# Sensors.net
KiCad netlist of a schematic drawn in Altium Designer
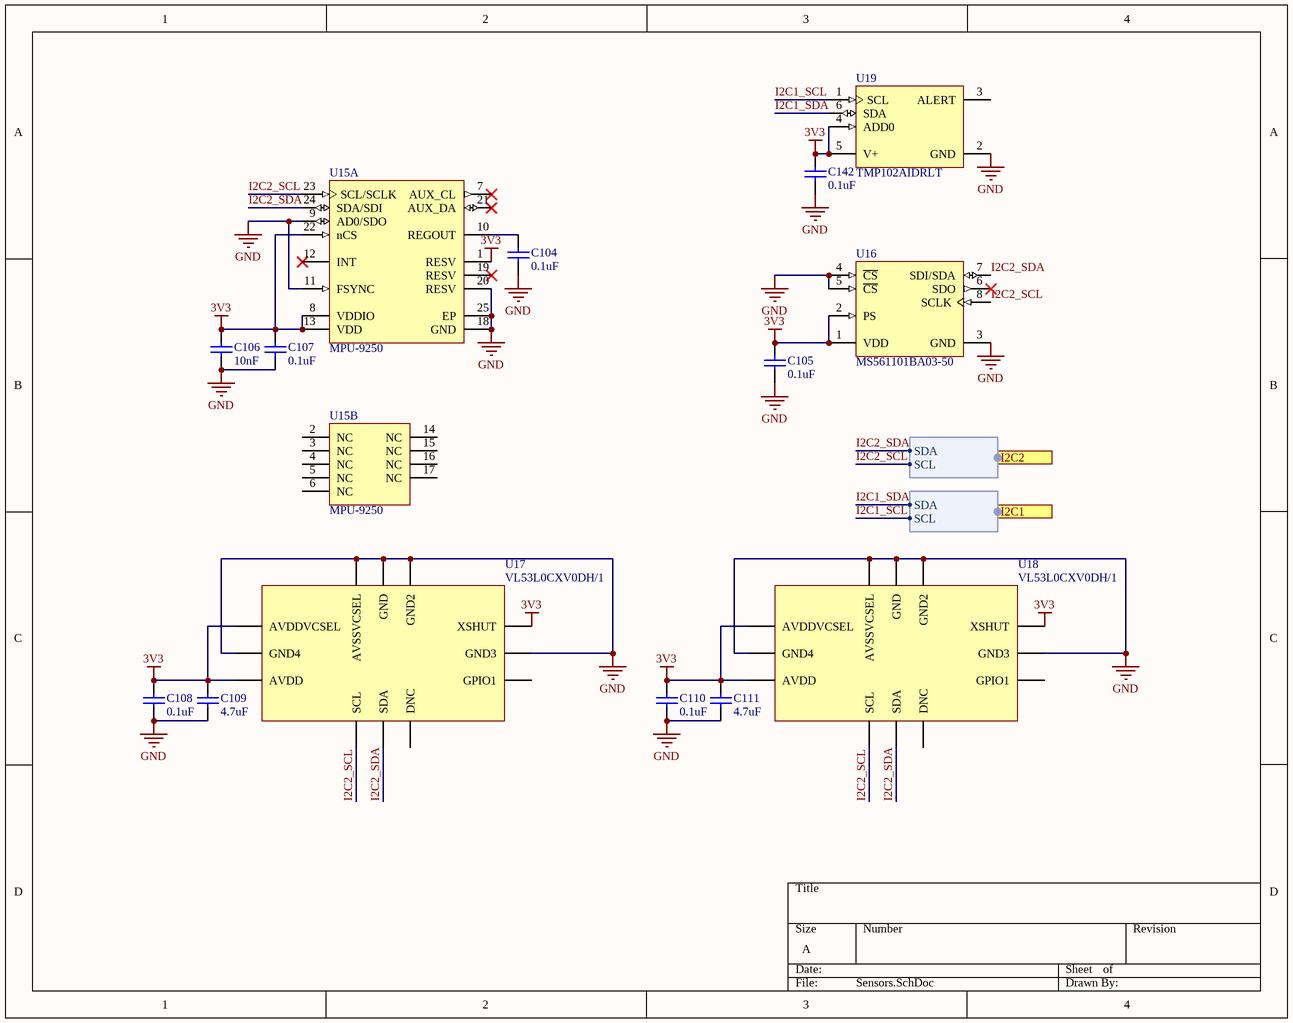
[diagram p0: Sensors.SchDoc]

(export (version "E")
  (design (tool "Eeschema 10.0.6"))
  (components
    (comp (ref "C104")
      (value "0.1uF")
      (footprint "C0402[1005X55]")
      (description "0.1uF 6.3V 10% 0402 (1005 Metric)")
      (fields (field (name "PARTNUMBER") "GRM155R70J104KA01D") (field (name "MANUFACTURER") "Murata"))
      (libsource (lib "Capacitors") (part "CAP_0.1uF_6.3V_0402_10%"))
    )
    (comp (ref "C105")
      (value "0.1uF")
      (footprint "C0402[1005X55]")
      (description "0.1uF 6.3V 10% 0402 (1005 Metric)")
      (fields (field (name "PARTNUMBER") "GRM155R70J104KA01D") (field (name "MANUFACTURER") "Murata"))
      (libsource (lib "Capacitors") (part "CAP_0.1uF_6.3V_0402_10%"))
    )
    (comp (ref "C106")
      (value "10nF")
      (footprint "C0402[1005X55]")
      (description "10nF 50V 10% 0402 (1005 Metric)")
      (fields (field (name "PARTNUMBER") "GCM155R71H103KA55D") (field (name "MANUFACTURER") "Murata"))
      (libsource (lib "Capacitors") (part "CAP_10nF_50V_0402_10%"))
    )
    (comp (ref "C107")
      (value "0.1uF")
      (footprint "C0402[1005X55]")
      (description "0.1uF 6.3V 10% 0402 (1005 Metric)")
      (fields (field (name "PARTNUMBER") "GRM155R70J104KA01D") (field (name "MANUFACTURER") "Murata"))
      (libsource (lib "Capacitors") (part "CAP_0.1uF_6.3V_0402_10%"))
    )
    (comp (ref "C108")
      (value "0.1uF")
      (footprint "C0402[1005X55]")
      (description "0.1uF 6.3V 10% 0402 (1005 Metric)")
      (fields (field (name "PARTNUMBER") "GRM155R70J104KA01D") (field (name "MANUFACTURER") "Murata"))
      (libsource (lib "Capacitors") (part "CAP_0.1uF_6.3V_0402_10%"))
    )
    (comp (ref "C109")
      (value "4.7uF")
      (footprint "C0402[1005X55]")
      (description "4.7uF 6.3V 20% 0402 (1005 Metric)")
      (fields (field (name "PARTNUMBER") "GRM155R60J475ME47D") (field (name "MANUFACTURER") "Murata"))
      (libsource (lib "Capacitors") (part "CAP_4.7uF_6.3V_0402_20%"))
    )
    (comp (ref "C110")
      (value "0.1uF")
      (footprint "C0402[1005X55]")
      (description "0.1uF 6.3V 10% 0402 (1005 Metric)")
      (fields (field (name "PARTNUMBER") "GRM155R70J104KA01D") (field (name "MANUFACTURER") "Murata"))
      (libsource (lib "Capacitors") (part "CAP_0.1uF_6.3V_0402_10%"))
    )
    (comp (ref "C111")
      (value "4.7uF")
      (footprint "C0402[1005X55]")
      (description "4.7uF 6.3V 20% 0402 (1005 Metric)")
      (fields (field (name "PARTNUMBER") "GRM155R60J475ME47D") (field (name "MANUFACTURER") "Murata"))
      (libsource (lib "Capacitors") (part "CAP_4.7uF_6.3V_0402_20%"))
    )
    (comp (ref "C142")
      (value "0.1uF")
      (footprint "C0402[1005X55]")
      (description "0.1uF 6.3V 10% 0402 (1005 Metric)")
      (fields (field (name "PARTNUMBER") "GRM155R70J104KA01D") (field (name "MANUFACTURER") "Murata"))
      (libsource (lib "Capacitors") (part "CAP_0.1uF_6.3V_0402_10%"))
    )
    (comp (ref "U15")
      (value "MPU-9250")
      (footprint "QFN-24 (0.4MM)")
      (fields (field (name "MANUFACTURER") "Invensense"))
      (libsource (lib "ICs") (part "MPU-9250"))
    )
    (comp (ref "U16")
      (value "MS561101BA03-50")
      (footprint "MSI-MS561101BA03-50-8_V")
      (fields (field (name "MANUFACTURER") "Measurement Specialties"))
      (libsource (lib "Altium Content Vault") (part "MSI-MS561101BA03-50-8"))
    )
    (comp (ref "U17")
      (value "VL53L0CXV0DH/1")
      (footprint "LGA-12")
      (description "Optical Sensor Modules Time-of-Flight (ToF) ranging sensor")
      (fields (field (name "MANUFACTURER") "STMicroelectronics"))
      (libsource (lib "ICs") (part "VL53L0CXV0DH/1"))
    )
    (comp (ref "U18")
      (value "VL53L0CXV0DH/1")
      (footprint "LGA-12")
      (description "Optical Sensor Modules Time-of-Flight (ToF) ranging sensor")
      (fields (field (name "MANUFACTURER") "STMicroelectronics"))
      (libsource (lib "ICs") (part "VL53L0CXV0DH/1"))
    )
    (comp (ref "U19")
      (value "TMP102AIDRLT")
      (footprint "DRL0006A_L")
      (libsource (lib "Altium Content Vault") (part "TI-TMP102AIDRLT-DRL6"))
    )
  )
  (nets
    (net (code "2") (name "/I2C1_SCL") (class "Default")
      (node (ref "U19") (pin "1") (pinfunction "SCL_1") (pintype "input"))
    )
    (net (code "3") (name "/I2C1_SDA") (class "Default")
      (node (ref "U19") (pin "6") (pinfunction "SDA_6") (pintype "bidirectional"))
    )
    (net (code "4") (name "/I2C2_SCL") (class "Default")
      (node (ref "U15") (pin "23") (pinfunction "SCL/SCLK_23") (pintype "input"))
      (node (ref "U16") (pin "8") (pinfunction "SCLK_8") (pintype "input"))
      (node (ref "U17") (pin "10") (pinfunction "SCL_10") (pintype "passive"))
      (node (ref "U18") (pin "10") (pinfunction "SCL_10") (pintype "passive"))
    )
    (net (code "5") (name "/I2C2_SDA") (class "Default")
      (node (ref "U15") (pin "24") (pinfunction "SDA/SDI_24") (pintype "bidirectional"))
      (node (ref "U16") (pin "7") (pinfunction "SDI/SDA_7") (pintype "bidirectional"))
      (node (ref "U17") (pin "9") (pinfunction "SDA_9") (pintype "passive"))
      (node (ref "U18") (pin "9") (pinfunction "SDA_9") (pintype "passive"))
    )
    (net (code "7") (name "3V3") (class "Default")
      (node (ref "C105") (pin "2") (pinfunction "2_2") (pintype "passive"))
      (node (ref "C106") (pin "2") (pinfunction "2_2") (pintype "passive"))
      (node (ref "C107") (pin "2") (pinfunction "2_2") (pintype "passive"))
      (node (ref "C108") (pin "2") (pinfunction "2_2") (pintype "passive"))
      (node (ref "C109") (pin "2") (pinfunction "2_2") (pintype "passive"))
      (node (ref "C110") (pin "2") (pinfunction "2_2") (pintype "passive"))
      (node (ref "C111") (pin "2") (pinfunction "2_2") (pintype "passive"))
      (node (ref "C142") (pin "2") (pinfunction "2_2") (pintype "passive"))
      (node (ref "U15") (pin "1") (pinfunction "RESV_1") (pintype "power_in"))
      (node (ref "U15") (pin "13") (pinfunction "VDD_13") (pintype "power_in"))
      (node (ref "U15") (pin "22") (pinfunction "nCS_22") (pintype "input"))
      (node (ref "U15") (pin "8") (pinfunction "VDDIO_8") (pintype "power_in"))
      (node (ref "U16") (pin "1") (pinfunction "VDD_1") (pintype "power_in"))
      (node (ref "U16") (pin "2") (pinfunction "PS_2") (pintype "input"))
      (node (ref "U17") (pin "1") (pinfunction "AVDDVCSEL_1") (pintype "passive"))
      (node (ref "U17") (pin "11") (pinfunction "AVDD_11") (pintype "passive"))
      (node (ref "U17") (pin "5") (pinfunction "XSHUT_5") (pintype "passive"))
      (node (ref "U18") (pin "1") (pinfunction "AVDDVCSEL_1") (pintype "passive"))
      (node (ref "U18") (pin "11") (pinfunction "AVDD_11") (pintype "passive"))
      (node (ref "U18") (pin "5") (pinfunction "XSHUT_5") (pintype "passive"))
      (node (ref "U19") (pin "4") (pinfunction "ADD0_4") (pintype "input"))
      (node (ref "U19") (pin "5") (pinfunction "V+_5") (pintype "power_in"))
    )
    (net (code "8") (name "GND") (class "Default")
      (node (ref "C104") (pin "1") (pinfunction "1_1") (pintype "passive"))
      (node (ref "C105") (pin "1") (pinfunction "1_1") (pintype "passive"))
      (node (ref "C106") (pin "1") (pinfunction "1_1") (pintype "passive"))
      (node (ref "C107") (pin "1") (pinfunction "1_1") (pintype "passive"))
      (node (ref "C108") (pin "1") (pinfunction "1_1") (pintype "passive"))
      (node (ref "C109") (pin "1") (pinfunction "1_1") (pintype "passive"))
      (node (ref "C110") (pin "1") (pinfunction "1_1") (pintype "passive"))
      (node (ref "C111") (pin "1") (pinfunction "1_1") (pintype "passive"))
      (node (ref "C142") (pin "1") (pinfunction "1_1") (pintype "passive"))
      (node (ref "U15") (pin "11") (pinfunction "FSYNC_11") (pintype "input"))
      (node (ref "U15") (pin "18") (pinfunction "GND_18") (pintype "power_in"))
      (node (ref "U15") (pin "20") (pinfunction "RESV_20") (pintype "power_in"))
      (node (ref "U15") (pin "25") (pinfunction "EP_25") (pintype "passive"))
      (node (ref "U15") (pin "9") (pinfunction "AD0/SDO_9") (pintype "bidirectional"))
      (node (ref "U16") (pin "3") (pinfunction "GND_3") (pintype "power_in"))
      (node (ref "U16") (pin "4") (pinfunction "~{CS}_4") (pintype "input"))
      (node (ref "U16") (pin "5") (pinfunction "~{CS}_5") (pintype "input"))
      (node (ref "U17") (pin "12") (pinfunction "GND4_12") (pintype "passive"))
      (node (ref "U17") (pin "2") (pinfunction "AVSSVCSEL_2") (pintype "passive"))
      (node (ref "U17") (pin "3") (pinfunction "GND_3") (pintype "passive"))
      (node (ref "U17") (pin "4") (pinfunction "GND2_4") (pintype "passive"))
      (node (ref "U17") (pin "6") (pinfunction "GND3_6") (pintype "passive"))
      (node (ref "U18") (pin "12") (pinfunction "GND4_12") (pintype "passive"))
      (node (ref "U18") (pin "2") (pinfunction "AVSSVCSEL_2") (pintype "passive"))
      (node (ref "U18") (pin "3") (pinfunction "GND_3") (pintype "passive"))
      (node (ref "U18") (pin "4") (pinfunction "GND2_4") (pintype "passive"))
      (node (ref "U18") (pin "6") (pinfunction "GND3_6") (pintype "passive"))
      (node (ref "U19") (pin "2") (pinfunction "GND_2") (pintype "power_in"))
    )
    (net (code "9") (name "Net-(U15A-REGOUT)") (class "Default")
      (node (ref "C104") (pin "2") (pinfunction "2_2") (pintype "passive"))
      (node (ref "U15") (pin "10") (pinfunction "REGOUT_10") (pintype "passive"))
    )
    (net (code "10") (name "unconnected-(U15A-AUX_CL-Pad7)") (class "Default")
      (node (ref "U15") (pin "7") (pinfunction "AUX_CL_7") (pintype "output+no_connect"))
    )
    (net (code "11") (name "unconnected-(U15A-AUX_DA-Pad21)") (class "Default")
      (node (ref "U15") (pin "21") (pinfunction "AUX_DA_21") (pintype "bidirectional+no_connect"))
    )
    (net (code "12") (name "unconnected-(U15A-INT-Pad12)") (class "Default")
      (node (ref "U15") (pin "12") (pinfunction "INT_12") (pintype "tri_state+no_connect"))
    )
    (net (code "13") (name "unconnected-(U15A-RESV-Pad19)") (class "Default")
      (node (ref "U15") (pin "19") (pinfunction "RESV_19") (pintype "passive+no_connect"))
    )
    (net (code "14") (name "unconnected-(U15B-NC-Pad2)") (class "Default")
      (node (ref "U15") (pin "2") (pinfunction "NC_2") (pintype "passive"))
    )
    (net (code "15") (name "unconnected-(U15B-NC-Pad3)") (class "Default")
      (node (ref "U15") (pin "3") (pinfunction "NC_3") (pintype "passive"))
    )
    (net (code "16") (name "unconnected-(U15B-NC-Pad4)") (class "Default")
      (node (ref "U15") (pin "4") (pinfunction "NC_4") (pintype "passive"))
    )
    (net (code "17") (name "unconnected-(U15B-NC-Pad5)") (class "Default")
      (node (ref "U15") (pin "5") (pinfunction "NC_5") (pintype "passive"))
    )
    (net (code "18") (name "unconnected-(U15B-NC-Pad6)") (class "Default")
      (node (ref "U15") (pin "6") (pinfunction "NC_6") (pintype "passive"))
    )
    (net (code "19") (name "unconnected-(U15B-NC-Pad14)") (class "Default")
      (node (ref "U15") (pin "14") (pinfunction "NC_14") (pintype "passive"))
    )
    (net (code "20") (name "unconnected-(U15B-NC-Pad15)") (class "Default")
      (node (ref "U15") (pin "15") (pinfunction "NC_15") (pintype "passive"))
    )
    (net (code "21") (name "unconnected-(U15B-NC-Pad16)") (class "Default")
      (node (ref "U15") (pin "16") (pinfunction "NC_16") (pintype "passive"))
    )
    (net (code "22") (name "unconnected-(U15B-NC-Pad17)") (class "Default")
      (node (ref "U15") (pin "17") (pinfunction "NC_17") (pintype "passive"))
    )
    (net (code "23") (name "unconnected-(U16-SDO-Pad6)") (class "Default")
      (node (ref "U16") (pin "6") (pinfunction "SDO_6") (pintype "output+no_connect"))
    )
    (net (code "24") (name "unconnected-(U17-DNC-Pad8)") (class "Default")
      (node (ref "U17") (pin "8") (pinfunction "DNC_8") (pintype "passive"))
    )
    (net (code "25") (name "unconnected-(U17-GPIO1-Pad7)") (class "Default")
      (node (ref "U17") (pin "7") (pinfunction "GPIO1_7") (pintype "passive"))
    )
    (net (code "26") (name "unconnected-(U18-DNC-Pad8)") (class "Default")
      (node (ref "U18") (pin "8") (pinfunction "DNC_8") (pintype "passive"))
    )
    (net (code "27") (name "unconnected-(U18-GPIO1-Pad7)") (class "Default")
      (node (ref "U18") (pin "7") (pinfunction "GPIO1_7") (pintype "passive"))
    )
    (net (code "28") (name "unconnected-(U19-ALERT-Pad3)") (class "Default")
      (node (ref "U19") (pin "3") (pinfunction "ALERT_3") (pintype "open_collector"))
    )
  )
)
